# Using_xSignals_in_a_High-Speed_Design_wi.net
KiCad netlist of a schematic drawn in Altium Designer
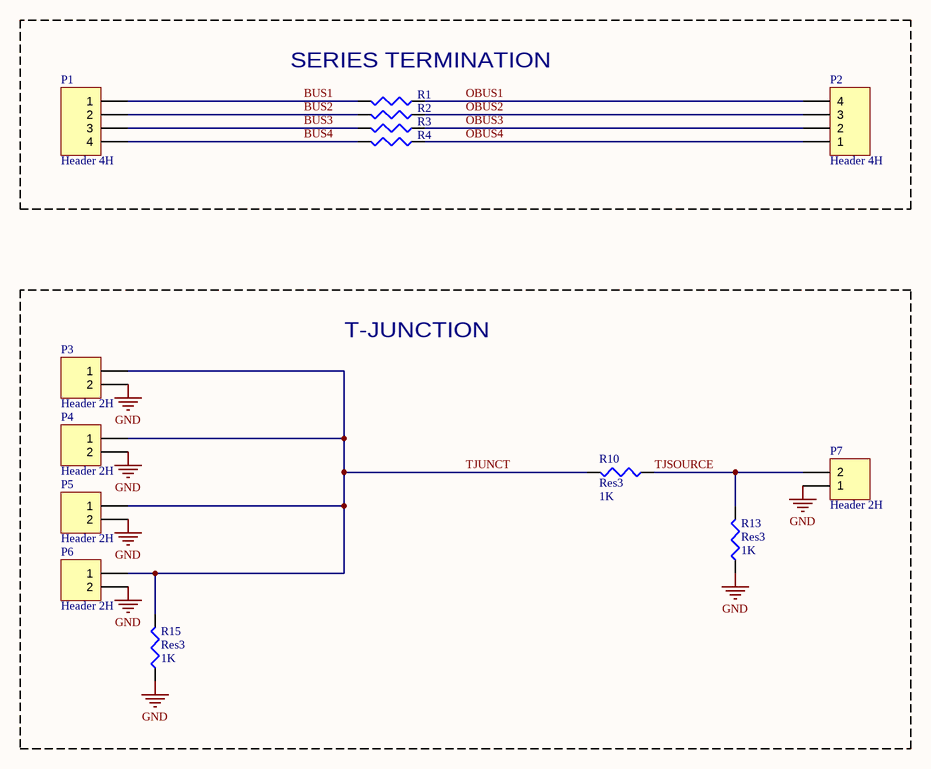
[diagram p0: Using xSignals in a High-Speed Design with CM.SchDoc]

(export (version "E")
  (design (tool "Eeschema 10.0.6"))
  (components
    (comp (ref "P1")
      (value "Header 4H")
      (footprint "HDR1X4H")
      (description "Header, 4-Pin, Right Angle")
      (fields (field (name "PUBLISHER") "Altium Limited"))
      (libsource (lib "") (part "Header 4H_1"))
    )
    (comp (ref "P2")
      (value "Header 4H")
      (footprint "HDR1X4H")
      (description "Header, 4-Pin, Right Angle")
      (fields (field (name "PUBLISHER") "Altium Limited"))
      (libsource (lib "Miscellaneous Connectors") (part "Header 4H"))
    )
    (comp (ref "P3")
      (value "Header 2H")
      (footprint "HDR1X2H")
      (description "Header, 2-Pin, Right Angle")
      (fields (field (name "PUBLISHER") "Altium Limited"))
      (libsource (lib "Miscellaneous Connectors") (part "Header 2H"))
    )
    (comp (ref "P4")
      (value "Header 2H")
      (footprint "HDR1X2H")
      (description "Header, 2-Pin, Right Angle")
      (fields (field (name "PUBLISHER") "Altium Limited"))
      (libsource (lib "Miscellaneous Connectors") (part "Header 2H"))
    )
    (comp (ref "P5")
      (value "Header 2H")
      (footprint "HDR1X2H")
      (description "Header, 2-Pin, Right Angle")
      (fields (field (name "PUBLISHER") "Altium Limited"))
      (libsource (lib "Miscellaneous Connectors") (part "Header 2H"))
    )
    (comp (ref "P6")
      (value "Header 2H")
      (footprint "HDR1X2H")
      (description "Header, 2-Pin, Right Angle")
      (fields (field (name "PUBLISHER") "Altium Limited"))
      (libsource (lib "Miscellaneous Connectors") (part "Header 2H"))
    )
    (comp (ref "P7")
      (value "Header 2H")
      (footprint "HDR1X2H")
      (description "Header, 2-Pin, Right Angle")
      (fields (field (name "PUBLISHER") "Altium Limited"))
      (libsource (lib "") (part "Header 2H_1"))
    )
    (comp (ref "R1")
      (value "Res3")
      (footprint "J1-0603")
      (description "Resistor")
      (fields (field (name "PUBLISHER") "Altium Limited"))
      (libsource (lib "Miscellaneous Devices") (part "Res3"))
    )
    (comp (ref "R2")
      (value "Res3")
      (footprint "J1-0603")
      (description "Resistor")
      (fields (field (name "PUBLISHER") "Altium Limited"))
      (libsource (lib "Miscellaneous Devices") (part "Res3"))
    )
    (comp (ref "R3")
      (value "Res3")
      (footprint "J1-0603")
      (description "Resistor")
      (fields (field (name "PUBLISHER") "Altium Limited"))
      (libsource (lib "Miscellaneous Devices") (part "Res3"))
    )
    (comp (ref "R4")
      (value "Res3")
      (footprint "J1-0603")
      (description "Resistor")
      (fields (field (name "PUBLISHER") "Altium Limited"))
      (libsource (lib "Miscellaneous Devices") (part "Res3"))
    )
    (comp (ref "R10")
      (value "Res3")
      (footprint "J1-0603")
      (description "Resistor")
      (fields (field (name "ALTIUM_VALUE") "1K") (field (name "PUBLISHER") "Altium Limited"))
      (libsource (lib "Miscellaneous Devices") (part "Res3"))
    )
    (comp (ref "R13")
      (value "Res3")
      (footprint "J1-0603")
      (description "Resistor")
      (fields (field (name "ALTIUM_VALUE") "1K") (field (name "PUBLISHER") "Altium Limited"))
      (libsource (lib "Miscellaneous Devices") (part "Res3"))
    )
    (comp (ref "R15")
      (value "Res3")
      (footprint "J1-0603")
      (description "Resistor")
      (fields (field (name "ALTIUM_VALUE") "1K") (field (name "PUBLISHER") "Altium Limited"))
      (libsource (lib "Miscellaneous Devices") (part "Res3"))
    )
  )
  (nets
    (net (code "1") (name "/BUS1") (class "Default")
      (node (ref "P1") (pin "1") (pinfunction "1_1") (pintype "passive"))
      (node (ref "R1") (pin "2") (pinfunction "2_2") (pintype "passive"))
    )
    (net (code "2") (name "/BUS2") (class "Default")
      (node (ref "P1") (pin "2") (pinfunction "2_2") (pintype "passive"))
      (node (ref "R2") (pin "2") (pinfunction "2_2") (pintype "passive"))
    )
    (net (code "3") (name "/BUS3") (class "Default")
      (node (ref "P1") (pin "3") (pinfunction "3_3") (pintype "passive"))
      (node (ref "R3") (pin "2") (pinfunction "2_2") (pintype "passive"))
    )
    (net (code "4") (name "/BUS4") (class "Default")
      (node (ref "P1") (pin "4") (pinfunction "4_4") (pintype "passive"))
      (node (ref "R4") (pin "2") (pinfunction "2_2") (pintype "passive"))
    )
    (net (code "5") (name "/OBUS1") (class "Default")
      (node (ref "P2") (pin "4") (pinfunction "4_4") (pintype "passive"))
      (node (ref "R1") (pin "1") (pinfunction "1_1") (pintype "passive"))
    )
    (net (code "6") (name "/OBUS2") (class "Default")
      (node (ref "P2") (pin "3") (pinfunction "3_3") (pintype "passive"))
      (node (ref "R2") (pin "1") (pinfunction "1_1") (pintype "passive"))
    )
    (net (code "7") (name "/OBUS3") (class "Default")
      (node (ref "P2") (pin "2") (pinfunction "2_2") (pintype "passive"))
      (node (ref "R3") (pin "1") (pinfunction "1_1") (pintype "passive"))
    )
    (net (code "8") (name "/OBUS4") (class "Default")
      (node (ref "P2") (pin "1") (pinfunction "1_1") (pintype "passive"))
      (node (ref "R4") (pin "1") (pinfunction "1_1") (pintype "passive"))
    )
    (net (code "9") (name "/TJSOURCE") (class "Default")
      (node (ref "P7") (pin "2") (pinfunction "2_2") (pintype "passive"))
      (node (ref "R10") (pin "1") (pinfunction "1_1") (pintype "passive"))
      (node (ref "R13") (pin "2") (pinfunction "2_2") (pintype "passive"))
    )
    (net (code "10") (name "/TJUNCT") (class "Default")
      (node (ref "P3") (pin "1") (pinfunction "1_1") (pintype "passive"))
      (node (ref "P4") (pin "1") (pinfunction "1_1") (pintype "passive"))
      (node (ref "P5") (pin "1") (pinfunction "1_1") (pintype "passive"))
      (node (ref "P6") (pin "1") (pinfunction "1_1") (pintype "passive"))
      (node (ref "R10") (pin "2") (pinfunction "2_2") (pintype "passive"))
      (node (ref "R15") (pin "2") (pinfunction "2_2") (pintype "passive"))
    )
    (net (code "11") (name "GND") (class "Default")
      (node (ref "P3") (pin "2") (pinfunction "2_2") (pintype "passive"))
      (node (ref "P4") (pin "2") (pinfunction "2_2") (pintype "passive"))
      (node (ref "P5") (pin "2") (pinfunction "2_2") (pintype "passive"))
      (node (ref "P6") (pin "2") (pinfunction "2_2") (pintype "passive"))
      (node (ref "P7") (pin "1") (pinfunction "1_1") (pintype "passive"))
      (node (ref "R13") (pin "1") (pinfunction "1_1") (pintype "passive"))
      (node (ref "R15") (pin "1") (pinfunction "1_1") (pintype "passive"))
    )
  )
)
